# bh.net
KiCad netlist of a schematic drawn in EAGLE
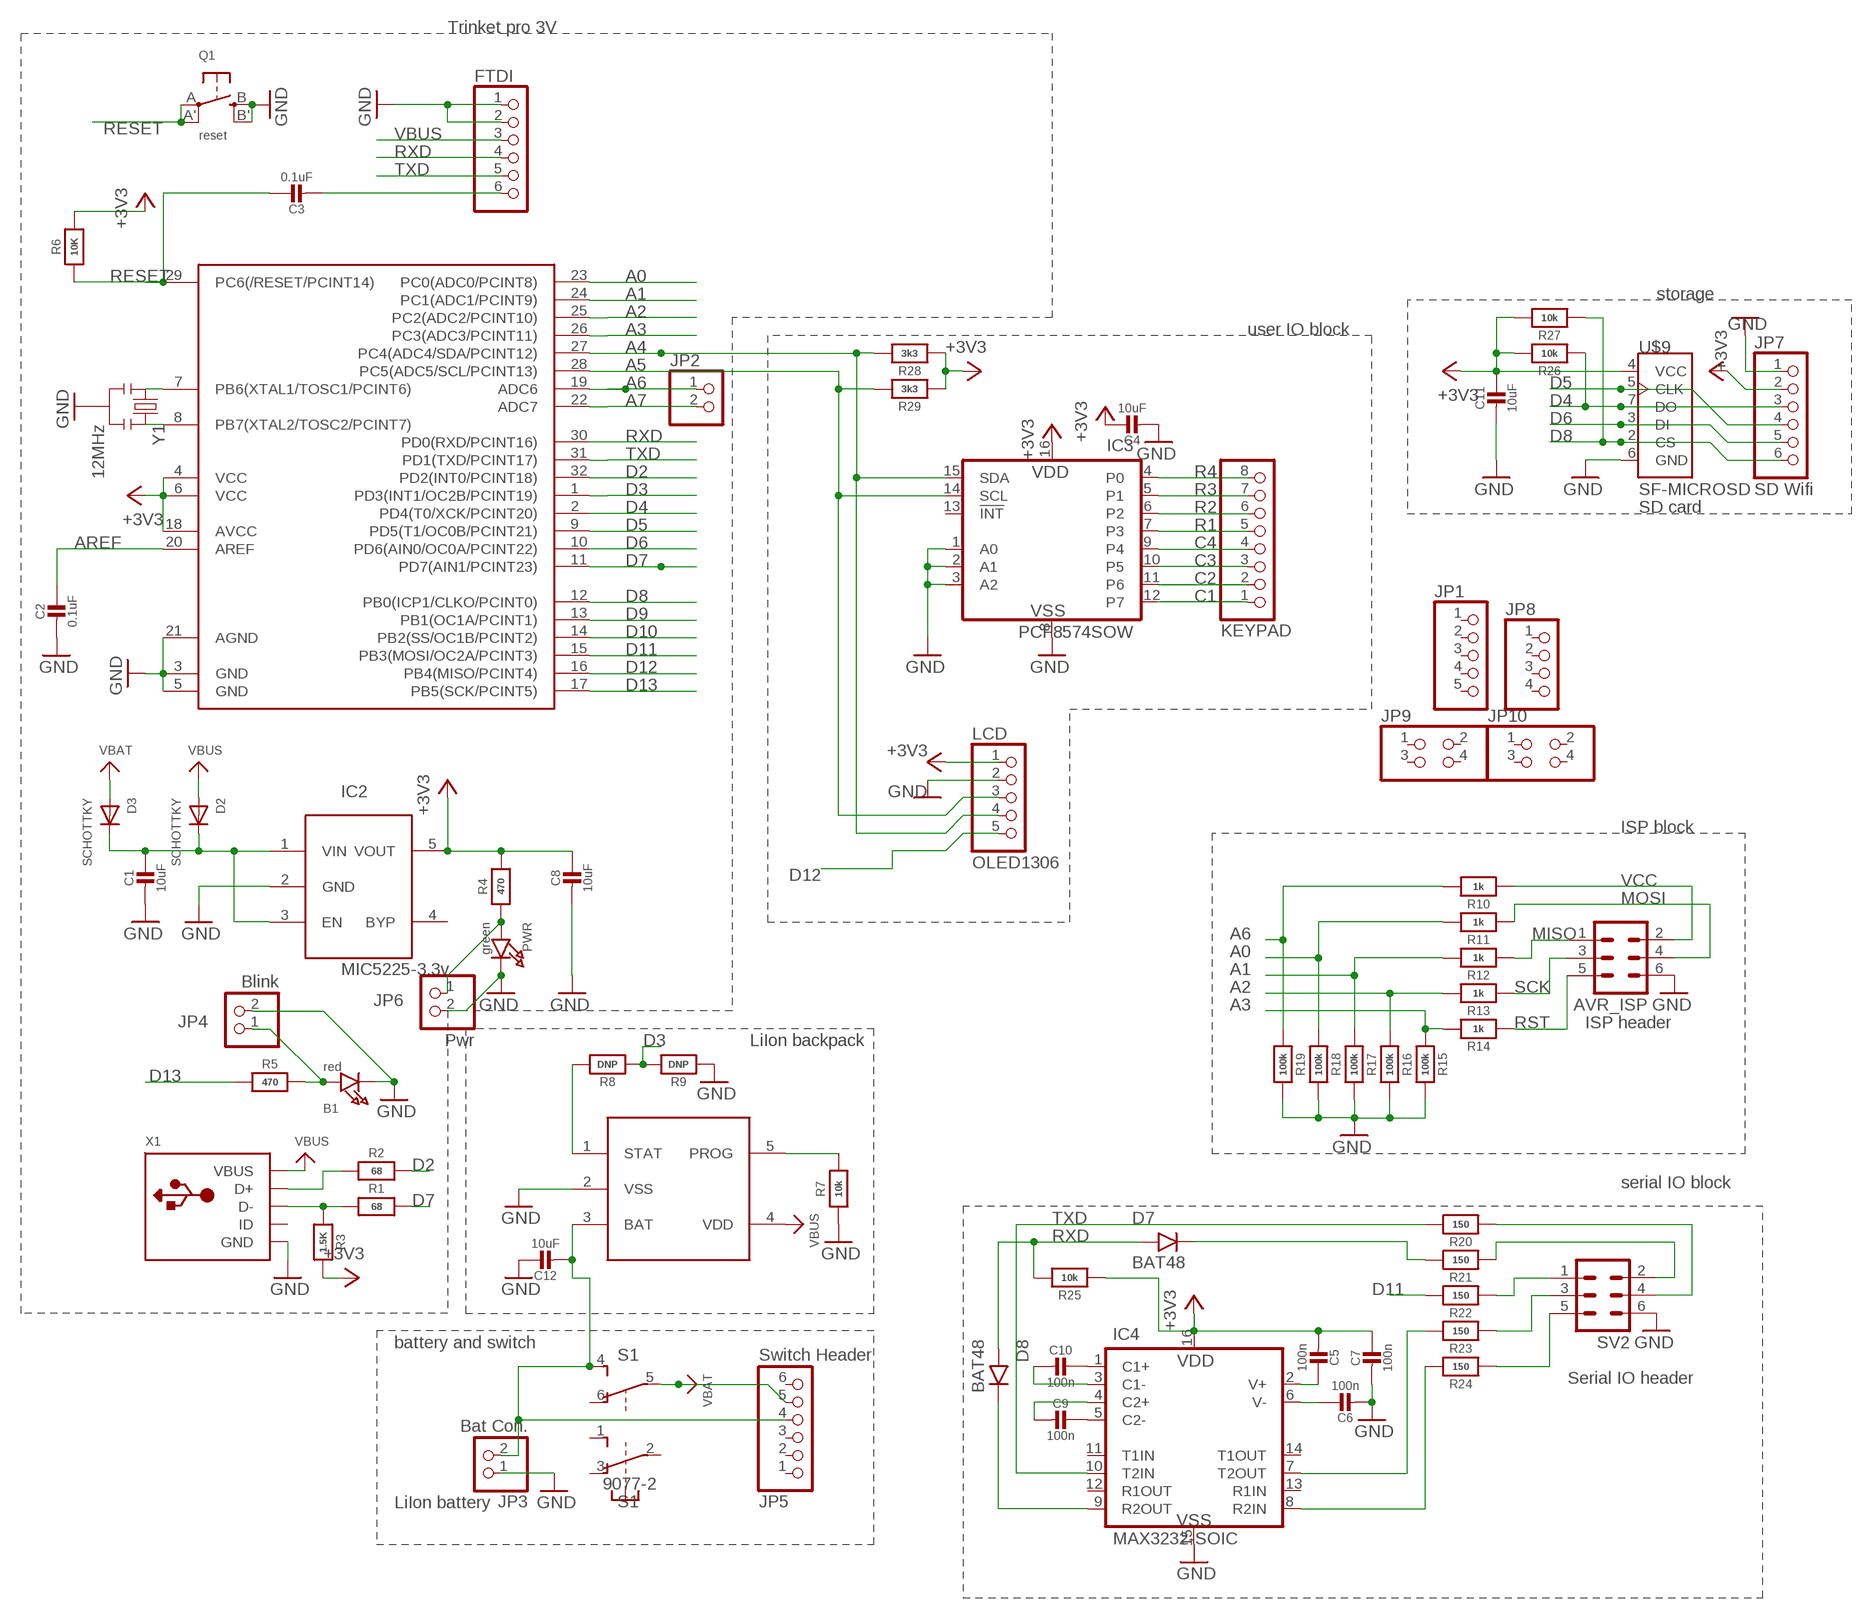
[diagram p0: schematic, sheet 1]

(export (version "E")
  (design (tool "Eeschema 10.0.6"))
  (components
    (comp (ref "AVR_ISP")
      (value "ML6")
      (footprint "eagle-import:ML6")
      (libsource (lib "eagle-import") (part "ML6"))
    )
    (comp (ref "B1")
      (value "red")
      (footprint "eagle-import:CHIPLED_0805_NOOUTLINE")
      (libsource (lib "eagle-import") (part "LED0805_NOOUTLINE"))
    )
    (comp (ref "C1")
      (value "10uF")
      (footprint "eagle-import:0805-NO")
      (libsource (lib "eagle-import") (part "CAP_CERAMIC0805-NOOUTLINE"))
    )
    (comp (ref "C2")
      (value "0.1uF")
      (footprint "eagle-import:_0805MP")
      (libsource (lib "eagle-import") (part "CAP_CERAMIC_0805MP"))
    )
    (comp (ref "C3")
      (value "0.1uF")
      (footprint "eagle-import:0805-NO")
      (libsource (lib "eagle-import") (part "CAP_CERAMIC0805-NOOUTLINE"))
    )
    (comp (ref "C4")
      (value "10uF")
      (footprint "eagle-import:0805-NO")
      (libsource (lib "eagle-import") (part "CAP_CERAMIC0805-NOOUTLINE"))
    )
    (comp (ref "C5")
      (value "100n")
      (footprint "eagle-import:0805-NO")
      (libsource (lib "eagle-import") (part "CAP_CERAMIC0805-NOOUTLINE"))
    )
    (comp (ref "C6")
      (value "100n")
      (footprint "eagle-import:0805-NO")
      (libsource (lib "eagle-import") (part "CAP_CERAMIC0805-NOOUTLINE"))
    )
    (comp (ref "C7")
      (value "100n")
      (footprint "eagle-import:0805-NO")
      (libsource (lib "eagle-import") (part "CAP_CERAMIC0805-NOOUTLINE"))
    )
    (comp (ref "C8")
      (value "10uF")
      (footprint "eagle-import:0805-NO")
      (libsource (lib "eagle-import") (part "CAP_CERAMIC0805-NOOUTLINE"))
    )
    (comp (ref "C9")
      (value "100n")
      (footprint "eagle-import:0805-NO")
      (libsource (lib "eagle-import") (part "CAP_CERAMIC0805-NOOUTLINE"))
    )
    (comp (ref "C10")
      (value "100n")
      (footprint "eagle-import:0805-NO")
      (libsource (lib "eagle-import") (part "CAP_CERAMIC0805-NOOUTLINE"))
    )
    (comp (ref "C11")
      (value "10uF")
      (footprint "eagle-import:0805-NO")
      (libsource (lib "eagle-import") (part "CAP_CERAMIC0805-NOOUTLINE"))
    )
    (comp (ref "C12")
      (value "10uF")
      (footprint "eagle-import:0805-NO")
      (libsource (lib "eagle-import") (part "CAP_CERAMIC0805-NOOUTLINE"))
    )
    (comp (ref "D2")
      (value "SCHOTTKY")
      (footprint "eagle-import:ADAFRUIT_SOD-123FL")
      (libsource (lib "eagle-import") (part "ADAFRUIT_DIODE_SOD-123FL"))
    )
    (comp (ref "D3")
      (value "SCHOTTKY")
      (footprint "eagle-import:ADAFRUIT_SOD-123FL")
      (libsource (lib "eagle-import") (part "ADAFRUIT_DIODE_SOD-123FL"))
    )
    (comp (ref "D7")
      (value "BAT48")
      (footprint "eagle-import:SOD-80")
      (libsource (lib "eagle-import") (part "1N4148SOD"))
    )
    (comp (ref "D8")
      (value "BAT48")
      (footprint "eagle-import:SOD-80")
      (libsource (lib "eagle-import") (part "1N4148SOD"))
    )
    (comp (ref "FTDI")
      (value "ADAFRUIT_PINHD-1X6CB")
      (footprint "eagle-import:ADAFRUIT_1X06-CLEANBIG")
      (libsource (lib "eagle-import") (part "ADAFRUIT_PINHD-1X6CB"))
    )
    (comp (ref "IC2")
      (value "MIC5225-3.3v")
      (footprint "eagle-import:SOT23-5L")
      (libsource (lib "eagle-import") (part "LP298XS"))
    )
    (comp (ref "IC3")
      (value "PCF8574SOW")
      (footprint "eagle-import:SO-16DW")
      (libsource (lib "eagle-import") (part "PCF8574SOW"))
    )
    (comp (ref "IC4")
      (value "MAX3232-SOIC")
      (footprint "eagle-import:SO-16")
      (libsource (lib "eagle-import") (part "MAX3232-SOIC"))
    )
    (comp (ref "IC5")
      (value "MEGA328P")
      (footprint "eagle-import:TQFP32-08")
      (libsource (lib "eagle-import") (part "MEGA48/88/168-AU"))
    )
    (comp (ref "JP1")
      (value "PINHD-1X5")
      (footprint "eagle-import:1X05")
      (libsource (lib "eagle-import") (part "PINHD-1X5"))
    )
    (comp (ref "JP2")
      (value "HEADER-1X2ROUND")
      (footprint "eagle-import:1X02_ROUND")
      (libsource (lib "eagle-import") (part "HEADER-1X2ROUND"))
    )
    (comp (ref "JP3")
      (value "Bat Con.")
      (footprint "eagle-import:1X02_90")
      (libsource (lib "eagle-import") (part "PINHD-1X02_2.54-90°"))
    )
    (comp (ref "JP4")
      (value "Blink")
      (footprint "eagle-import:1X02")
      (libsource (lib "eagle-import") (part "PINHD-1X2"))
    )
    (comp (ref "JP5")
      (value "Switch Header")
      (footprint "eagle-import:1X06")
      (libsource (lib "eagle-import") (part "PINHD-1X6"))
    )
    (comp (ref "JP6")
      (value "Pwr")
      (footprint "eagle-import:1X02")
      (libsource (lib "eagle-import") (part "PINHD-1X2"))
    )
    (comp (ref "JP7")
      (value "SD Wifi")
      (footprint "eagle-import:1X06")
      (libsource (lib "eagle-import") (part "PINHD-1X6"))
    )
    (comp (ref "JP8")
      (value "PINHD-1X4")
      (footprint "eagle-import:1X04")
      (libsource (lib "eagle-import") (part "PINHD-1X4"))
    )
    (comp (ref "JP9")
      (value "PINHD-2X2")
      (footprint "eagle-import:2X02")
      (libsource (lib "eagle-import") (part "PINHD-2X2"))
    )
    (comp (ref "JP10")
      (value "PINHD-2X2")
      (footprint "eagle-import:2X02")
      (libsource (lib "eagle-import") (part "PINHD-2X2"))
    )
    (comp (ref "KEYPAD")
      (value "PINHD-1X8")
      (footprint "eagle-import:1X08")
      (libsource (lib "eagle-import") (part "PINHD-1X8"))
    )
    (comp (ref "LCD")
      (value "OLED1306")
      (footprint "eagle-import:1X05")
      (libsource (lib "eagle-import") (part "PINHD-1X5"))
    )
    (comp (ref "PWR")
      (value "green")
      (footprint "eagle-import:CHIPLED_0805_NOOUTLINE")
      (libsource (lib "eagle-import") (part "LED0805_NOOUTLINE"))
    )
    (comp (ref "Q1")
      (value "reset")
      (footprint "eagle-import:BTN_KMR2_4.6X2.8")
      (libsource (lib "eagle-import") (part "SWITCH_TACT_SMT4.6X2.8"))
    )
    (comp (ref "R1")
      (value "68")
      (footprint "eagle-import:0603-NO")
      (libsource (lib "eagle-import") (part "RESISTOR_0603_NOOUT"))
    )
    (comp (ref "R2")
      (value "68")
      (footprint "eagle-import:0603-NO")
      (libsource (lib "eagle-import") (part "RESISTOR_0603_NOOUT"))
    )
    (comp (ref "R3")
      (value "1.5K")
      (footprint "eagle-import:0603-NO")
      (libsource (lib "eagle-import") (part "RESISTOR_0603_NOOUT"))
    )
    (comp (ref "R4")
      (value "470")
      (footprint "eagle-import:0603-NO")
      (libsource (lib "eagle-import") (part "RESISTOR_0603_NOOUT"))
    )
    (comp (ref "R5")
      (value "470")
      (footprint "eagle-import:0603-NO")
      (libsource (lib "eagle-import") (part "RESISTOR_0603_NOOUT"))
    )
    (comp (ref "R6")
      (value "10K")
      (footprint "eagle-import:0805-NO")
      (libsource (lib "eagle-import") (part "RESISTOR0805_NOOUTLINE"))
    )
    (comp (ref "R7")
      (value "10k")
      (footprint "eagle-import:_0805")
      (libsource (lib "eagle-import") (part "RESISTOR_0805"))
    )
    (comp (ref "R8")
      (value "DNP")
      (footprint "eagle-import:_0805")
      (libsource (lib "eagle-import") (part "RESISTOR_0805"))
    )
    (comp (ref "R9")
      (value "DNP")
      (footprint "eagle-import:_0805")
      (libsource (lib "eagle-import") (part "RESISTOR_0805"))
    )
    (comp (ref "R10")
      (value "1k")
      (footprint "eagle-import:_0805")
      (libsource (lib "eagle-import") (part "RESISTOR_0805"))
    )
    (comp (ref "R11")
      (value "1k")
      (footprint "eagle-import:_0805")
      (libsource (lib "eagle-import") (part "RESISTOR_0805"))
    )
    (comp (ref "R12")
      (value "1k")
      (footprint "eagle-import:_0805")
      (libsource (lib "eagle-import") (part "RESISTOR_0805"))
    )
    (comp (ref "R13")
      (value "1k")
      (footprint "eagle-import:_0805")
      (libsource (lib "eagle-import") (part "RESISTOR_0805"))
    )
    (comp (ref "R14")
      (value "1k")
      (footprint "eagle-import:_0805")
      (libsource (lib "eagle-import") (part "RESISTOR_0805"))
    )
    (comp (ref "R15")
      (value "100k")
      (footprint "eagle-import:_0805")
      (libsource (lib "eagle-import") (part "RESISTOR_0805"))
    )
    (comp (ref "R16")
      (value "100k")
      (footprint "eagle-import:_0805")
      (libsource (lib "eagle-import") (part "RESISTOR_0805"))
    )
    (comp (ref "R17")
      (value "100k")
      (footprint "eagle-import:_0805")
      (libsource (lib "eagle-import") (part "RESISTOR_0805"))
    )
    (comp (ref "R18")
      (value "100k")
      (footprint "eagle-import:_0805")
      (libsource (lib "eagle-import") (part "RESISTOR_0805"))
    )
    (comp (ref "R19")
      (value "100k")
      (footprint "eagle-import:_0805")
      (libsource (lib "eagle-import") (part "RESISTOR_0805"))
    )
    (comp (ref "R20")
      (value "150")
      (footprint "eagle-import:_0805")
      (libsource (lib "eagle-import") (part "RESISTOR_0805"))
    )
    (comp (ref "R21")
      (value "150")
      (footprint "eagle-import:_0805")
      (libsource (lib "eagle-import") (part "RESISTOR_0805"))
    )
    (comp (ref "R22")
      (value "150")
      (footprint "eagle-import:_0805")
      (libsource (lib "eagle-import") (part "RESISTOR_0805"))
    )
    (comp (ref "R23")
      (value "150")
      (footprint "eagle-import:_0805")
      (libsource (lib "eagle-import") (part "RESISTOR_0805"))
    )
    (comp (ref "R24")
      (value "150")
      (footprint "eagle-import:_0805")
      (libsource (lib "eagle-import") (part "RESISTOR_0805"))
    )
    (comp (ref "R25")
      (value "10k")
      (footprint "eagle-import:_0805")
      (libsource (lib "eagle-import") (part "RESISTOR_0805"))
    )
    (comp (ref "R26")
      (value "10k")
      (footprint "eagle-import:_0805")
      (libsource (lib "eagle-import") (part "RESISTOR_0805"))
    )
    (comp (ref "R27")
      (value "10k")
      (footprint "eagle-import:_0805")
      (libsource (lib "eagle-import") (part "RESISTOR_0805"))
    )
    (comp (ref "R28")
      (value "3k3")
      (footprint "eagle-import:_0805")
      (libsource (lib "eagle-import") (part "RESISTOR_0805"))
    )
    (comp (ref "R29")
      (value "3k3")
      (footprint "eagle-import:_0805")
      (libsource (lib "eagle-import") (part "RESISTOR_0805"))
    )
    (comp (ref "S1")
      (value "9077-2")
      (footprint "eagle-import:9077-2")
      (libsource (lib "eagle-import") (part "9077-2"))
    )
    (comp (ref "SV2")
      (value "ML6")
      (footprint "eagle-import:ML6")
      (libsource (lib "eagle-import") (part "ML6"))
    )
    (comp (ref "U$6")
      (value "MCP73831")
      (footprint "eagle-import:SOT23-5")
      (libsource (lib "eagle-import") (part "MCP73831"))
    )
    (comp (ref "U$9")
      (value "SF-MICROSD")
      (footprint "eagle-import:MICROSD")
      (libsource (lib "eagle-import") (part "SF-MICROSD"))
    )
    (comp (ref "X1")
      (value "MICROBUILDER_USBMICRO_20329")
      (footprint "eagle-import:MICROBUILDER_4UCONN_20329")
      (libsource (lib "eagle-import") (part "MICROBUILDER_USBMICRO_20329"))
    )
    (comp (ref "Y1")
      (value "12MHz")
      (footprint "eagle-import:RESONATOR-SMD")
      (libsource (lib "eagle-import") (part "RESONATORSMD"))
    )
  )
  (nets
    (net (code "1") (name "+3V3") (class "Default")
      (node (ref "C11") (pin "1") (pinfunction "1_1") (pintype "passive"))
      (node (ref "C4") (pin "1") (pinfunction "1_1") (pintype "passive"))
      (node (ref "C5") (pin "2") (pinfunction "2_2") (pintype "passive"))
      (node (ref "C7") (pin "1") (pinfunction "1_1") (pintype "passive"))
      (node (ref "C8") (pin "1") (pinfunction "1_1") (pintype "passive"))
      (node (ref "IC2") (pin "5") (pinfunction "VOUT_5") (pintype "bidirectional"))
      (node (ref "IC3") (pin "16") (pinfunction "VDD_16") (pintype "power_in"))
      (node (ref "IC4") (pin "16") (pinfunction "VDD_16") (pintype "power_in"))
      (node (ref "IC5") (pin "18") (pinfunction "AVCC_18") (pintype "passive"))
      (node (ref "IC5") (pin "4") (pinfunction "VCC_4") (pintype "power_in"))
      (node (ref "IC5") (pin "6") (pinfunction "VCC_6") (pintype "power_in"))
      (node (ref "JP7") (pin "2") (pinfunction "2_2") (pintype "passive"))
      (node (ref "LCD") (pin "1") (pinfunction "1_1") (pintype "passive"))
      (node (ref "R25") (pin "2") (pinfunction "2_2") (pintype "passive"))
      (node (ref "R26") (pin "1") (pinfunction "1_1") (pintype "passive"))
      (node (ref "R27") (pin "1") (pinfunction "1_1") (pintype "passive"))
      (node (ref "R28") (pin "2") (pinfunction "2_2") (pintype "passive"))
      (node (ref "R29") (pin "2") (pinfunction "2_2") (pintype "passive"))
      (node (ref "R3") (pin "2") (pinfunction "2_2") (pintype "passive"))
      (node (ref "R4") (pin "2") (pinfunction "2_2") (pintype "passive"))
      (node (ref "R6") (pin "2") (pinfunction "2_2") (pintype "passive"))
      (node (ref "U$9") (pin "4") (pinfunction "VCC_4") (pintype "passive"))
    )
    (net (code "2") (name "/A0") (class "Default")
      (node (ref "IC5") (pin "23") (pinfunction "PC0(ADC0/PCINT8)_23") (pintype "bidirectional"))
      (node (ref "R11") (pin "1") (pinfunction "1_1") (pintype "passive"))
      (node (ref "R18") (pin "2") (pinfunction "2_2") (pintype "passive"))
    )
    (net (code "3") (name "/A1") (class "Default")
      (node (ref "IC5") (pin "24") (pinfunction "PC1(ADC1/PCINT9)_24") (pintype "bidirectional"))
      (node (ref "R12") (pin "1") (pinfunction "1_1") (pintype "passive"))
      (node (ref "R17") (pin "2") (pinfunction "2_2") (pintype "passive"))
    )
    (net (code "4") (name "/A2") (class "Default")
      (node (ref "IC5") (pin "25") (pinfunction "PC2(ADC2/PCINT10)_25") (pintype "bidirectional"))
      (node (ref "R13") (pin "1") (pinfunction "1_1") (pintype "passive"))
      (node (ref "R16") (pin "2") (pinfunction "2_2") (pintype "passive"))
    )
    (net (code "5") (name "/A3") (class "Default")
      (node (ref "IC5") (pin "26") (pinfunction "PC3(ADC3/PCINT11)_26") (pintype "bidirectional"))
      (node (ref "R14") (pin "1") (pinfunction "1_1") (pintype "passive"))
      (node (ref "R15") (pin "2") (pinfunction "2_2") (pintype "passive"))
    )
    (net (code "6") (name "/A4") (class "Default")
      (node (ref "IC3") (pin "15") (pinfunction "SDA_15") (pintype "bidirectional"))
      (node (ref "IC5") (pin "27") (pinfunction "PC4(ADC4/SDA/PCINT12)_27") (pintype "bidirectional"))
      (node (ref "LCD") (pin "4") (pinfunction "4_4") (pintype "passive"))
      (node (ref "R28") (pin "1") (pinfunction "1_1") (pintype "passive"))
    )
    (net (code "7") (name "/A5") (class "Default")
      (node (ref "IC3") (pin "14") (pinfunction "SCL_14") (pintype "bidirectional"))
      (node (ref "IC5") (pin "28") (pinfunction "PC5(ADC5/SCL/PCINT13)_28") (pintype "bidirectional"))
      (node (ref "LCD") (pin "3") (pinfunction "3_3") (pintype "passive"))
      (node (ref "R29") (pin "1") (pinfunction "1_1") (pintype "passive"))
    )
    (net (code "8") (name "/A6") (class "Default")
      (node (ref "IC5") (pin "19") (pinfunction "ADC6_19") (pintype "passive"))
      (node (ref "JP2") (pin "1") (pinfunction "1_1") (pintype "passive"))
      (node (ref "R10") (pin "1") (pinfunction "1_1") (pintype "passive"))
      (node (ref "R19") (pin "2") (pinfunction "2_2") (pintype "passive"))
    )
    (net (code "9") (name "/A7") (class "Default")
      (node (ref "IC5") (pin "22") (pinfunction "ADC7_22") (pintype "passive"))
      (node (ref "JP2") (pin "2") (pinfunction "2_2") (pintype "passive"))
    )
    (net (code "10") (name "/AREF") (class "Default")
      (node (ref "C2") (pin "1") (pinfunction "1_1") (pintype "passive"))
      (node (ref "IC5") (pin "20") (pinfunction "AREF_20") (pintype "passive"))
    )
    (net (code "11") (name "/C1") (class "Default")
      (node (ref "IC3") (pin "12") (pinfunction "P7_12") (pintype "bidirectional"))
      (node (ref "KEYPAD") (pin "1") (pinfunction "1_1") (pintype "passive"))
    )
    (net (code "12") (name "/C2") (class "Default")
      (node (ref "IC3") (pin "11") (pinfunction "P6_11") (pintype "bidirectional"))
      (node (ref "KEYPAD") (pin "2") (pinfunction "2_2") (pintype "passive"))
    )
    (net (code "13") (name "/C3") (class "Default")
      (node (ref "IC3") (pin "10") (pinfunction "P5_10") (pintype "bidirectional"))
      (node (ref "KEYPAD") (pin "3") (pinfunction "3_3") (pintype "passive"))
    )
    (net (code "14") (name "/C4") (class "Default")
      (node (ref "IC3") (pin "9") (pinfunction "P4_9") (pintype "bidirectional"))
      (node (ref "KEYPAD") (pin "4") (pinfunction "4_4") (pintype "passive"))
    )
    (net (code "15") (name "/D2") (class "Default")
      (node (ref "IC5") (pin "32") (pinfunction "PD2(INT0/PCINT18)_32") (pintype "bidirectional"))
      (node (ref "R2") (pin "2") (pinfunction "2_2") (pintype "passive"))
    )
    (net (code "16") (name "/D3") (class "Default")
      (node (ref "IC5") (pin "1") (pinfunction "PD3(INT1/OC2B/PCINT19)_1") (pintype "bidirectional"))
      (node (ref "R8") (pin "2") (pinfunction "2_2") (pintype "passive"))
      (node (ref "R9") (pin "1") (pinfunction "1_1") (pintype "passive"))
    )
    (net (code "17") (name "/D4") (class "Default")
      (node (ref "IC5") (pin "2") (pinfunction "PD4(T0/XCK/PCINT20)_2") (pintype "bidirectional"))
      (node (ref "JP7") (pin "3") (pinfunction "3_3") (pintype "passive"))
      (node (ref "R26") (pin "2") (pinfunction "2_2") (pintype "passive"))
      (node (ref "U$9") (pin "7") (pinfunction "DO_7") (pintype "bidirectional"))
    )
    (net (code "18") (name "/D5") (class "Default")
      (node (ref "IC5") (pin "9") (pinfunction "PD5(T1/OC0B/PCINT21)_9") (pintype "bidirectional"))
      (node (ref "JP7") (pin "4") (pinfunction "4_4") (pintype "passive"))
      (node (ref "U$9") (pin "5") (pinfunction "CLK_5") (pintype "bidirectional"))
    )
    (net (code "19") (name "/D6") (class "Default")
      (node (ref "IC5") (pin "10") (pinfunction "PD6(AIN0/OC0A/PCINT22)_10") (pintype "bidirectional"))
      (node (ref "JP7") (pin "5") (pinfunction "5_5") (pintype "passive"))
      (node (ref "U$9") (pin "3") (pinfunction "DI_3") (pintype "bidirectional"))
    )
    (net (code "20") (name "/D7") (class "Default")
      (node (ref "IC5") (pin "11") (pinfunction "PD7(AIN1/PCINT23)_11") (pintype "bidirectional"))
      (node (ref "R1") (pin "2") (pinfunction "2_2") (pintype "passive"))
    )
    (net (code "21") (name "/D8") (class "Default")
      (node (ref "IC5") (pin "12") (pinfunction "PB0(ICP1/CLKO/PCINT0)_12") (pintype "bidirectional"))
      (node (ref "JP7") (pin "6") (pinfunction "6_6") (pintype "passive"))
      (node (ref "R27") (pin "2") (pinfunction "2_2") (pintype "passive"))
      (node (ref "U$9") (pin "2") (pinfunction "CS_2") (pintype "bidirectional"))
    )
    (net (code "22") (name "/D9") (class "Default")
      (node (ref "IC5") (pin "13") (pinfunction "PB1(OC1A/PCINT1)_13") (pintype "bidirectional"))
    )
    (net (code "23") (name "/D10") (class "Default")
      (node (ref "IC5") (pin "14") (pinfunction "PB2(SS/OC1B/PCINT2)_14") (pintype "bidirectional"))
    )
    (net (code "24") (name "/D11") (class "Default")
      (node (ref "IC5") (pin "15") (pinfunction "PB3(MOSI/OC2A/PCINT3)_15") (pintype "bidirectional"))
      (node (ref "R22") (pin "1") (pinfunction "1_1") (pintype "passive"))
    )
    (net (code "25") (name "/D12") (class "Default")
      (node (ref "IC5") (pin "16") (pinfunction "PB4(MISO/PCINT4)_16") (pintype "bidirectional"))
      (node (ref "LCD") (pin "5") (pinfunction "5_5") (pintype "passive"))
    )
    (net (code "26") (name "/D13") (class "Default")
      (node (ref "IC5") (pin "17") (pinfunction "PB5(SCK/PCINT5)_17") (pintype "bidirectional"))
      (node (ref "R5") (pin "2") (pinfunction "2_2") (pintype "passive"))
    )
    (net (code "27") (name "/MISO") (class "Default")
      (node (ref "AVR_ISP") (pin "1") (pinfunction "1_1") (pintype "passive"))
      (node (ref "R12") (pin "2") (pinfunction "2_2") (pintype "passive"))
    )
    (net (code "28") (name "/MOSI") (class "Default")
      (node (ref "AVR_ISP") (pin "4") (pinfunction "4_4") (pintype "passive"))
      (node (ref "R11") (pin "2") (pinfunction "2_2") (pintype "passive"))
    )
    (net (code "29") (name "/R1") (class "Default")
      (node (ref "IC3") (pin "7") (pinfunction "P3_7") (pintype "bidirectional"))
      (node (ref "KEYPAD") (pin "5") (pinfunction "5_5") (pintype "passive"))
    )
    (net (code "30") (name "/R2") (class "Default")
      (node (ref "IC3") (pin "6") (pinfunction "P2_6") (pintype "bidirectional"))
      (node (ref "KEYPAD") (pin "6") (pinfunction "6_6") (pintype "passive"))
    )
    (net (code "31") (name "/R3") (class "Default")
      (node (ref "IC3") (pin "5") (pinfunction "P1_5") (pintype "bidirectional"))
      (node (ref "KEYPAD") (pin "7") (pinfunction "7_7") (pintype "passive"))
    )
    (net (code "32") (name "/R4") (class "Default")
      (node (ref "IC3") (pin "4") (pinfunction "P0_4") (pintype "bidirectional"))
      (node (ref "KEYPAD") (pin "8") (pinfunction "8_8") (pintype "passive"))
    )
    (net (code "33") (name "/RESET") (class "Default")
      (node (ref "C3") (pin "1") (pinfunction "1_1") (pintype "passive"))
      (node (ref "IC5") (pin "29") (pinfunction "PC6(/RESET/PCINT14)_29") (pintype "bidirectional"))
      (node (ref "Q1") (pin "A") (pinfunction "P_A") (pintype "passive"))
      (node (ref "Q1") (pin "A'") (pinfunction "P1_A'") (pintype "passive"))
      (node (ref "R6") (pin "1") (pinfunction "1_1") (pintype "passive"))
    )
    (net (code "34") (name "/RST") (class "Default")
      (node (ref "AVR_ISP") (pin "5") (pinfunction "5_5") (pintype "passive"))
      (node (ref "R14") (pin "2") (pinfunction "2_2") (pintype "passive"))
    )
    (net (code "35") (name "/RXD") (class "Default")
      (node (ref "D7") (pin "A") (pinfunction "A_A") (pintype "input"))
      (node (ref "D8") (pin "A") (pinfunction "A_A") (pintype "input"))
      (node (ref "FTDI") (pin "4") (pinfunction "4_4") (pintype "passive"))
      (node (ref "IC5") (pin "30") (pinfunction "PD0(RXD/PCINT16)_30") (pintype "bidirectional"))
      (node (ref "R25") (pin "1") (pinfunction "1_1") (pintype "passive"))
    )
    (net (code "36") (name "/SCK") (class "Default")
      (node (ref "AVR_ISP") (pin "3") (pinfunction "3_3") (pintype "passive"))
      (node (ref "R13") (pin "2") (pinfunction "2_2") (pintype "passive"))
    )
    (net (code "37") (name "/TXD") (class "Default")
      (node (ref "FTDI") (pin "5") (pinfunction "5_5") (pintype "passive"))
      (node (ref "IC4") (pin "10") (pinfunction "T2IN_10") (pintype "input"))
      (node (ref "IC5") (pin "31") (pinfunction "PD1(TXD/PCINT17)_31") (pintype "bidirectional"))
      (node (ref "R20") (pin "1") (pinfunction "1_1") (pintype "passive"))
    )
    (net (code "38") (name "/VCC") (class "Default")
      (node (ref "AVR_ISP") (pin "2") (pinfunction "2_2") (pintype "passive"))
      (node (ref "R10") (pin "2") (pinfunction "2_2") (pintype "passive"))
    )
    (net (code "39") (name "GND") (class "Default")
      (node (ref "AVR_ISP") (pin "6") (pinfunction "6_6") (pintype "passive"))
      (node (ref "B1") (pin "C") (pinfunction "C_C") (pintype "passive"))
      (node (ref "C1") (pin "2") (pinfunction "2_2") (pintype "passive"))
      (node (ref "C11") (pin "2") (pinfunction "2_2") (pintype "passive"))
      (node (ref "C12") (pin "1") (pinfunction "1_1") (pintype "passive"))
      (node (ref "C2") (pin "2") (pinfunction "2_2") (pintype "passive"))
      (node (ref "C4") (pin "2") (pinfunction "2_2") (pintype "passive"))
      (node (ref "C6") (pin "2") (pinfunction "2_2") (pintype "passive"))
      (node (ref "C7") (pin "2") (pinfunction "2_2") (pintype "passive"))
      (node (ref "C8") (pin "2") (pinfunction "2_2") (pintype "passive"))
      (node (ref "FTDI") (pin "1") (pinfunction "1_1") (pintype "passive"))
      (node (ref "FTDI") (pin "2") (pinfunction "2_2") (pintype "passive"))
      (node (ref "IC2") (pin "2") (pinfunction "GND_2") (pintype "bidirectional"))
      (node (ref "IC3") (pin "1") (pinfunction "A0_1") (pintype "bidirectional"))
      (node (ref "IC3") (pin "2") (pinfunction "A1_2") (pintype "bidirectional"))
      (node (ref "IC3") (pin "3") (pinfunction "A2_3") (pintype "bidirectional"))
      (node (ref "IC3") (pin "8") (pinfunction "VSS_8") (pintype "power_in"))
      (node (ref "IC4") (pin "15") (pinfunction "VSS_15") (pintype "power_in"))
      (node (ref "IC5") (pin "21") (pinfunction "AGND_21") (pintype "power_in"))
      (node (ref "IC5") (pin "3") (pinfunction "GND_3") (pintype "power_in"))
      (node (ref "IC5") (pin "5") (pinfunction "GND_5") (pintype "power_in"))
      (node (ref "JP3") (pin "1") (pinfunction "1_1") (pintype "passive"))
      (node (ref "JP4") (pin "2") (pinfunction "2_2") (pintype "passive"))
      (node (ref "JP6") (pin "2") (pinfunction "2_2") (pintype "passive"))
      (node (ref "JP7") (pin "1") (pinfunction "1_1") (pintype "passive"))
      (node (ref "LCD") (pin "2") (pinfunction "2_2") (pintype "passive"))
      (node (ref "PWR") (pin "C") (pinfunction "C_C") (pintype "passive"))
      (node (ref "Q1") (pin "B") (pinfunction "S_B") (pintype "passive"))
      (node (ref "Q1") (pin "B'") (pinfunction "S1_B'") (pintype "passive"))
      (node (ref "R15") (pin "1") (pinfunction "1_1") (pintype "passive"))
      (node (ref "R16") (pin "1") (pinfunction "1_1") (pintype "passive"))
      (node (ref "R17") (pin "1") (pinfunction "1_1") (pintype "passive"))
      (node (ref "R18") (pin "1") (pinfunction "1_1") (pintype "passive"))
      (node (ref "R19") (pin "1") (pinfunction "1_1") (pintype "passive"))
      (node (ref "R7") (pin "2") (pinfunction "2_2") (pintype "passive"))
      (node (ref "R9") (pin "2") (pinfunction "2_2") (pintype "passive"))
      (node (ref "SV2") (pin "6") (pinfunction "6_6") (pintype "passive"))
      (node (ref "U$6") (pin "2") (pinfunction "VSS_2") (pintype "bidirectional"))
      (node (ref "U$9") (pin "6") (pinfunction "GND_6") (pintype "power_in"))
      (node (ref "X1") (pin "BASE@1") (pinfunction "GND_BASE@1") (pintype "power_in"))
      (node (ref "X1") (pin "BASE@2") (pinfunction "GND_BASE@2") (pintype "power_in"))
      (node (ref "X1") (pin "GND") (pinfunction "GND_GND") (pintype "power_in"))
      (node (ref "X1") (pin "SPRT@1") (pinfunction "GND_SPRT@1") (pintype "power_in"))
      (node (ref "X1") (pin "SPRT@2") (pinfunction "GND_SPRT@2") (pintype "power_in"))
      (node (ref "X1") (pin "SPRT@3") (pinfunction "GND_SPRT@3") (pintype "power_in"))
      (node (ref "X1") (pin "SPRT@4") (pinfunction "GND_SPRT@4") (pintype "power_in"))
      (node (ref "Y1") (pin "2") (pinfunction "2_2") (pintype "passive"))
    )
    (net (code "40") (name "Net-(B1-PadA)") (class "Default")
      (node (ref "B1") (pin "A") (pinfunction "A_A") (pintype "passive"))
      (node (ref "JP4") (pin "1") (pinfunction "1_1") (pintype "passive"))
      (node (ref "R5") (pin "1") (pinfunction "1_1") (pintype "passive"))
    )
    (net (code "41") (name "Net-(C3-Pad2)") (class "Default")
      (node (ref "C3") (pin "2") (pinfunction "2_2") (pintype "passive"))
      (node (ref "FTDI") (pin "6") (pinfunction "6_6") (pintype "passive"))
    )
    (net (code "42") (name "Net-(D7-PadK)") (class "Default")
      (node (ref "D7") (pin "K") (pinfunction "K_K") (pintype "output"))
      (node (ref "R21") (pin "1") (pinfunction "1_1") (pintype "passive"))
    )
    (net (code "43") (name "Net-(IC2-EN)") (class "Default")
      (node (ref "C1") (pin "1") (pinfunction "1_1") (pintype "passive"))
      (node (ref "D2") (pin "C") (pinfunction "C_C") (pintype "passive"))
      (node (ref "D3") (pin "C") (pinfunction "C_C") (pintype "passive"))
      (node (ref "IC2") (pin "1") (pinfunction "VIN_1") (pintype "bidirectional"))
      (node (ref "IC2") (pin "3") (pinfunction "EN_3") (pintype "bidirectional"))
    )
    (net (code "44") (name "Net-(IC4-C1+)") (class "Default")
      (node (ref "C10") (pin "1") (pinfunction "1_1") (pintype "passive"))
      (node (ref "IC4") (pin "1") (pinfunction "C1+_1") (pintype "bidirectional"))
    )
    (net (code "45") (name "Net-(IC4-C1-)") (class "Default")
      (node (ref "C10") (pin "2") (pinfunction "2_2") (pintype "passive"))
      (node (ref "IC4") (pin "3") (pinfunction "C1-_3") (pintype "bidirectional"))
    )
    (net (code "46") (name "Net-(IC4-C2+)") (class "Default")
      (node (ref "C9") (pin "2") (pinfunction "2_2") (pintype "passive"))
      (node (ref "IC4") (pin "4") (pinfunction "C2+_4") (pintype "bidirectional"))
    )
    (net (code "47") (name "Net-(IC4-C2-)") (class "Default")
      (node (ref "C9") (pin "1") (pinfunction "1_1") (pintype "passive"))
      (node (ref "IC4") (pin "5") (pinfunction "C2-_5") (pintype "bidirectional"))
    )
    (net (code "48") (name "Net-(IC4-R2IN)") (class "Default")
      (node (ref "IC4") (pin "8") (pinfunction "R2IN_8") (pintype "output"))
      (node (ref "R24") (pin "1") (pinfunction "1_1") (pintype "passive"))
    )
    (net (code "49") (name "Net-(IC4-R2OUT)") (class "Default")
      (node (ref "D8") (pin "K") (pinfunction "K_K") (pintype "output"))
      (node (ref "IC4") (pin "9") (pinfunction "R2OUT_9") (pintype "input"))
    )
    (net (code "50") (name "Net-(IC4-T2OUT)") (class "Default")
      (node (ref "IC4") (pin "7") (pinfunction "T2OUT_7") (pintype "output"))
      (node (ref "R23") (pin "1") (pinfunction "1_1") (pintype "passive"))
    )
    (net (code "51") (name "Net-(IC4-V+)") (class "Default")
      (node (ref "C5") (pin "1") (pinfunction "1_1") (pintype "passive"))
      (node (ref "IC4") (pin "2") (pinfunction "V+_2") (pintype "bidirectional"))
    )
    (net (code "52") (name "Net-(IC4-V-)") (class "Default")
      (node (ref "C6") (pin "1") (pinfunction "1_1") (pintype "passive"))
      (node (ref "IC4") (pin "6") (pinfunction "V-_6") (pintype "bidirectional"))
    )
    (net (code "53") (name "Net-(IC5-PB6(XTAL1{slash}TOSC1{slash}PCINT6))") (class "Default")
      (node (ref "IC5") (pin "7") (pinfunction "PB6(XTAL1/TOSC1/PCINT6)_7") (pintype "bidirectional"))
      (node (ref "Y1") (pin "1") (pinfunction "1_1") (pintype "passive"))
    )
    (net (code "54") (name "Net-(IC5-PB7(XTAL2{slash}TOSC2{slash}PCINT7))") (class "Default")
      (node (ref "IC5") (pin "8") (pinfunction "PB7(XTAL2/TOSC2/PCINT7)_8") (pintype "bidirectional"))
      (node (ref "Y1") (pin "3") (pinfunction "3_3") (pintype "passive"))
    )
    (net (code "55") (name "Net-(JP6-Pad1)") (class "Default")
      (node (ref "JP6") (pin "1") (pinfunction "1_1") (pintype "passive"))
      (node (ref "PWR") (pin "A") (pinfunction "A_A") (pintype "passive"))
      (node (ref "R4") (pin "1") (pinfunction "1_1") (pintype "passive"))
    )
    (net (code "56") (name "Net-(R1-Pad1)") (class "Default")
      (node (ref "R1") (pin "1") (pinfunction "1_1") (pintype "passive"))
      (node (ref "R3") (pin "1") (pinfunction "1_1") (pintype "passive"))
      (node (ref "X1") (pin "D-") (pinfunction "D-_D-") (pintype "bidirectional"))
    )
    (net (code "57") (name "Net-(R2-Pad1)") (class "Default")
      (node (ref "R2") (pin "1") (pinfunction "1_1") (pintype "passive"))
      (node (ref "X1") (pin "D+") (pinfunction "D+_D+") (pintype "bidirectional"))
    )
    (net (code "58") (name "Net-(R20-Pad2)") (class "Default")
      (node (ref "R20") (pin "2") (pinfunction "2_2") (pintype "passive"))
      (node (ref "SV2") (pin "4") (pinfunction "4_4") (pintype "passive"))
    )
    (net (code "59") (name "Net-(R21-Pad2)") (class "Default")
      (node (ref "R21") (pin "2") (pinfunction "2_2") (pintype "passive"))
      (node (ref "SV2") (pin "2") (pinfunction "2_2") (pintype "passive"))
    )
    (net (code "60") (name "Net-(R22-Pad2)") (class "Default")
      (node (ref "R22") (pin "2") (pinfunction "2_2") (pintype "passive"))
      (node (ref "SV2") (pin "1") (pinfunction "1_1") (pintype "passive"))
    )
    (net (code "61") (name "Net-(R23-Pad2)") (class "Default")
      (node (ref "R23") (pin "2") (pinfunction "2_2") (pintype "passive"))
      (node (ref "SV2") (pin "3") (pinfunction "3_3") (pintype "passive"))
    )
    (net (code "62") (name "Net-(R24-Pad2)") (class "Default")
      (node (ref "R24") (pin "2") (pinfunction "2_2") (pintype "passive"))
      (node (ref "SV2") (pin "5") (pinfunction "5_5") (pintype "passive"))
    )
    (net (code "63") (name "Net-(S1B-S)") (class "Default")
      (node (ref "C12") (pin "2") (pinfunction "2_2") (pintype "passive"))
      (node (ref "JP3") (pin "2") (pinfunction "2_2") (pintype "passive"))
      (node (ref "JP5") (pin "4") (pinfunction "4_4") (pintype "passive"))
      (node (ref "S1") (pin "4") (pinfunction "S_4") (pintype "passive"))
      (node (ref "U$6") (pin "3") (pinfunction "BAT_3") (pintype "bidirectional"))
    )
    (net (code "64") (name "Net-(U$6-PROG)") (class "Default")
      (node (ref "R7") (pin "1") (pinfunction "1_1") (pintype "passive"))
      (node (ref "U$6") (pin "5") (pinfunction "PROG_5") (pintype "bidirectional"))
    )
    (net (code "65") (name "Net-(U$6-STAT)") (class "Default")
      (node (ref "R8") (pin "1") (pinfunction "1_1") (pintype "passive"))
      (node (ref "U$6") (pin "1") (pinfunction "STAT_1") (pintype "bidirectional"))
    )
    (net (code "66") (name "VBAT") (class "Default")
      (node (ref "D3") (pin "A") (pinfunction "A_A") (pintype "passive"))
      (node (ref "JP5") (pin "5") (pinfunction "5_5") (pintype "passive"))
      (node (ref "S1") (pin "5") (pinfunction "P_5") (pintype "passive"))
    )
    (net (code "67") (name "VBUS") (class "Default")
      (node (ref "D2") (pin "A") (pinfunction "A_A") (pintype "passive"))
      (node (ref "FTDI") (pin "3") (pinfunction "3_3") (pintype "passive"))
      (node (ref "U$6") (pin "4") (pinfunction "VDD_4") (pintype "bidirectional"))
      (node (ref "X1") (pin "VBUS") (pinfunction "VBUS_VBUS") (pintype "power_in"))
    )
    (net (code "68") (name "unconnected-(IC2-BYP-Pad4)") (class "Default")
      (node (ref "IC2") (pin "4") (pinfunction "BYP_4") (pintype "bidirectional"))
    )
    (net (code "69") (name "unconnected-(IC3-~{INT}-Pad13)") (class "Default")
      (node (ref "IC3") (pin "13") (pinfunction "~{INT}_13") (pintype "bidirectional"))
    )
    (net (code "70") (name "unconnected-(IC4-R1IN-Pad13)") (class "Default")
      (node (ref "IC4") (pin "13") (pinfunction "R1IN_13") (pintype "output"))
    )
    (net (code "71") (name "unconnected-(IC4-R1OUT-Pad12)") (class "Default")
      (node (ref "IC4") (pin "12") (pinfunction "R1OUT_12") (pintype "input"))
    )
    (net (code "72") (name "unconnected-(IC4-T1IN-Pad11)") (class "Default")
      (node (ref "IC4") (pin "11") (pinfunction "T1IN_11") (pintype "input"))
    )
    (net (code "73") (name "unconnected-(IC4-T1OUT-Pad14)") (class "Default")
      (node (ref "IC4") (pin "14") (pinfunction "T1OUT_14") (pintype "output"))
    )
    (net (code "74") (name "unconnected-(JP1-Pad1)") (class "Default")
      (node (ref "JP1") (pin "1") (pinfunction "1_1") (pintype "passive"))
    )
    (net (code "75") (name "unconnected-(JP1-Pad2)") (class "Default")
      (node (ref "JP1") (pin "2") (pinfunction "2_2") (pintype "passive"))
    )
    (net (code "76") (name "unconnected-(JP1-Pad3)") (class "Default")
      (node (ref "JP1") (pin "3") (pinfunction "3_3") (pintype "passive"))
    )
    (net (code "77") (name "unconnected-(JP1-Pad4)") (class "Default")
      (node (ref "JP1") (pin "4") (pinfunction "4_4") (pintype "passive"))
    )
    (net (code "78") (name "unconnected-(JP1-Pad5)") (class "Default")
      (node (ref "JP1") (pin "5") (pinfunction "5_5") (pintype "passive"))
    )
    (net (code "79") (name "unconnected-(JP5-Pad1)") (class "Default")
      (node (ref "JP5") (pin "1") (pinfunction "1_1") (pintype "passive"))
    )
    (net (code "80") (name "unconnected-(JP5-Pad2)") (class "Default")
      (node (ref "JP5") (pin "2") (pinfunction "2_2") (pintype "passive"))
    )
    (net (code "81") (name "unconnected-(JP5-Pad3)") (class "Default")
      (node (ref "JP5") (pin "3") (pinfunction "3_3") (pintype "passive"))
    )
    (net (code "82") (name "unconnected-(JP5-Pad6)") (class "Default")
      (node (ref "JP5") (pin "6") (pinfunction "6_6") (pintype "passive"))
    )
    (net (code "83") (name "unconnected-(JP8-Pad1)") (class "Default")
      (node (ref "JP8") (pin "1") (pinfunction "1_1") (pintype "passive"))
    )
    (net (code "84") (name "unconnected-(JP8-Pad2)") (class "Default")
      (node (ref "JP8") (pin "2") (pinfunction "2_2") (pintype "passive"))
    )
    (net (code "85") (name "unconnected-(JP8-Pad3)") (class "Default")
      (node (ref "JP8") (pin "3") (pinfunction "3_3") (pintype "passive"))
    )
    (net (code "86") (name "unconnected-(JP8-Pad4)") (class "Default")
      (node (ref "JP8") (pin "4") (pinfunction "4_4") (pintype "passive"))
    )
    (net (code "87") (name "unconnected-(JP9-Pad1)") (class "Default")
      (node (ref "JP9") (pin "1") (pinfunction "1_1") (pintype "passive"))
    )
    (net (code "88") (name "unconnected-(JP9-Pad2)") (class "Default")
      (node (ref "JP9") (pin "2") (pinfunction "2_2") (pintype "passive"))
    )
    (net (code "89") (name "unconnected-(JP9-Pad3)") (class "Default")
      (node (ref "JP9") (pin "3") (pinfunction "3_3") (pintype "passive"))
    )
    (net (code "90") (name "unconnected-(JP9-Pad4)") (class "Default")
      (node (ref "JP9") (pin "4") (pinfunction "4_4") (pintype "passive"))
    )
    (net (code "91") (name "unconnected-(JP10-Pad1)") (class "Default")
      (node (ref "JP10") (pin "1") (pinfunction "1_1") (pintype "passive"))
    )
    (net (code "92") (name "unconnected-(JP10-Pad2)") (class "Default")
      (node (ref "JP10") (pin "2") (pinfunction "2_2") (pintype "passive"))
    )
    (net (code "93") (name "unconnected-(JP10-Pad3)") (class "Default")
      (node (ref "JP10") (pin "3") (pinfunction "3_3") (pintype "passive"))
    )
    (net (code "94") (name "unconnected-(JP10-Pad4)") (class "Default")
      (node (ref "JP10") (pin "4") (pinfunction "4_4") (pintype "passive"))
    )
    (net (code "95") (name "unconnected-(S1A-O-Pad3)") (class "Default")
      (node (ref "S1") (pin "3") (pinfunction "O_3") (pintype "passive"))
    )
    (net (code "96") (name "unconnected-(S1A-P-Pad2)") (class "Default")
      (node (ref "S1") (pin "2") (pinfunction "P_2") (pintype "passive"))
    )
    (net (code "97") (name "unconnected-(S1A-S-Pad1)") (class "Default")
      (node (ref "S1") (pin "1") (pinfunction "S_1") (pintype "passive"))
    )
    (net (code "98") (name "unconnected-(S1B-O-Pad6)") (class "Default")
      (node (ref "S1") (pin "6") (pinfunction "O_6") (pintype "passive"))
    )
    (net (code "99") (name "unconnected-(X1-PadID)") (class "Default")
      (node (ref "X1") (pin "ID") (pinfunction "ID_ID") (pintype "bidirectional"))
    )
  )
)
